# Dualshock-3-type-C__schematic.net
KiCad netlist of a schematic drawn in Altium Designer
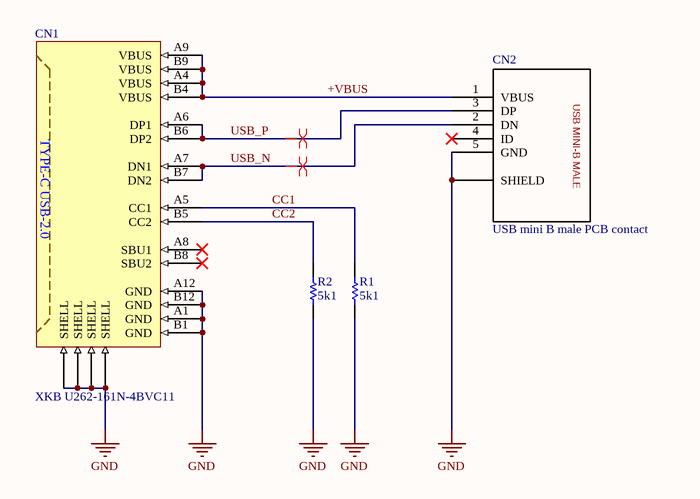
[diagram p0: Dualshock-3-type-C._schematic.SchDoc]

(export (version "E")
  (design (tool "Eeschema 10.0.6"))
  (components
    (comp (ref "CN1")
      (value "XKB U262-161N-4BVC11")
      (footprint "XKB U262-161N-4BVC11 - minimalPads")
      (description "USB Type-C connector, USB-2.0, 16 pins")
      (libsource (lib "planinsekLib_sch") (part "XKB U262-161N-4BVC11"))
    )
    (comp (ref "CN2")
      (value "USB mini B male PCB contact")
      (footprint "USB mini B male PCB contact")
      (libsource (lib "planinsekLib_sch") (part "USB mini B male PCB contact"))
    )
    (comp (ref "R1")
      (value "5k1")
      (footprint "RESC1005X40X25LL10T10")
      (fields (field (name "PART NUMBER") "0402WGF5101TCE") (field (name "MANUFACTURER") "UNI-ROYAL"))
      (libsource (lib "Altium Content Vault") (part "RES"))
    )
    (comp (ref "R2")
      (value "5k1")
      (footprint "RESC1005X40X25LL10T10")
      (fields (field (name "PART NUMBER") "0402WGF5101TCE") (field (name "MANUFACTURER") "UNI-ROYAL"))
      (libsource (lib "Altium Content Vault") (part "RES"))
    )
  )
  (nets
    (net (code "1") (name "/+VBUS") (class "Default")
      (node (ref "CN1") (pin "A4") (pinfunction "VBUS_A4") (pintype "input"))
      (node (ref "CN1") (pin "A9") (pinfunction "VBUS_A9") (pintype "input"))
      (node (ref "CN1") (pin "B4") (pinfunction "VBUS_B4") (pintype "input"))
      (node (ref "CN1") (pin "B9") (pinfunction "VBUS_B9") (pintype "input"))
      (node (ref "CN2") (pin "1") (pinfunction "VBUS_1") (pintype "passive"))
    )
    (net (code "2") (name "/CC1") (class "Default")
      (node (ref "CN1") (pin "A5") (pinfunction "CC1_A5") (pintype "input"))
      (node (ref "R1") (pin "2") (pinfunction "2_2") (pintype "passive"))
    )
    (net (code "3") (name "/CC2") (class "Default")
      (node (ref "CN1") (pin "B5") (pinfunction "CC2_B5") (pintype "input"))
      (node (ref "R2") (pin "2") (pinfunction "2_2") (pintype "passive"))
    )
    (net (code "4") (name "/USB_N") (class "Default")
      (node (ref "CN1") (pin "A7") (pinfunction "DN1_A7") (pintype "input"))
      (node (ref "CN1") (pin "B7") (pinfunction "DN2_B7") (pintype "input"))
      (node (ref "CN2") (pin "2") (pinfunction "DN_2") (pintype "passive"))
    )
    (net (code "5") (name "/USB_P") (class "Default")
      (node (ref "CN1") (pin "A6") (pinfunction "DP1_A6") (pintype "input"))
      (node (ref "CN1") (pin "B6") (pinfunction "DP2_B6") (pintype "input"))
      (node (ref "CN2") (pin "3") (pinfunction "DP_3") (pintype "passive"))
    )
    (net (code "6") (name "GND") (class "Default")
      (node (ref "CN1") (pin "A1") (pinfunction "GND_A1") (pintype "input"))
      (node (ref "CN1") (pin "A12") (pinfunction "GND_A12") (pintype "input"))
      (node (ref "CN1") (pin "B1") (pinfunction "GND_B1") (pintype "input"))
      (node (ref "CN1") (pin "B12") (pinfunction "GND_B12") (pintype "input"))
      (node (ref "CN1") (pin "SHELL1") (pinfunction "SHELL_SHELL1") (pintype "input"))
      (node (ref "CN1") (pin "SHELL2") (pinfunction "SHELL_SHELL2") (pintype "input"))
      (node (ref "CN1") (pin "SHELL3") (pinfunction "SHELL_SHELL3") (pintype "input"))
      (node (ref "CN1") (pin "SHELL4") (pinfunction "SHELL_SHELL4") (pintype "input"))
      (node (ref "CN2") (pin "5") (pinfunction "GND_5") (pintype "passive"))
      (node (ref "CN2") (pin "6") (pinfunction "SHIELD_6") (pintype "passive"))
      (node (ref "R1") (pin "1") (pinfunction "1_1") (pintype "passive"))
      (node (ref "R2") (pin "1") (pinfunction "1_1") (pintype "passive"))
    )
    (net (code "7") (name "unconnected-(CN1-SBU1-PadA8)") (class "Default")
      (node (ref "CN1") (pin "A8") (pinfunction "SBU1_A8") (pintype "input+no_connect"))
    )
    (net (code "8") (name "unconnected-(CN1-SBU2-PadB8)") (class "Default")
      (node (ref "CN1") (pin "B8") (pinfunction "SBU2_B8") (pintype "input+no_connect"))
    )
    (net (code "9") (name "unconnected-(CN2-ID-Pad4)") (class "Default")
      (node (ref "CN2") (pin "4") (pinfunction "ID_4") (pintype "passive+no_connect"))
    )
  )
)
